# Soldeerboute.net
KiCad netlist of a schematic drawn in Altium Designer
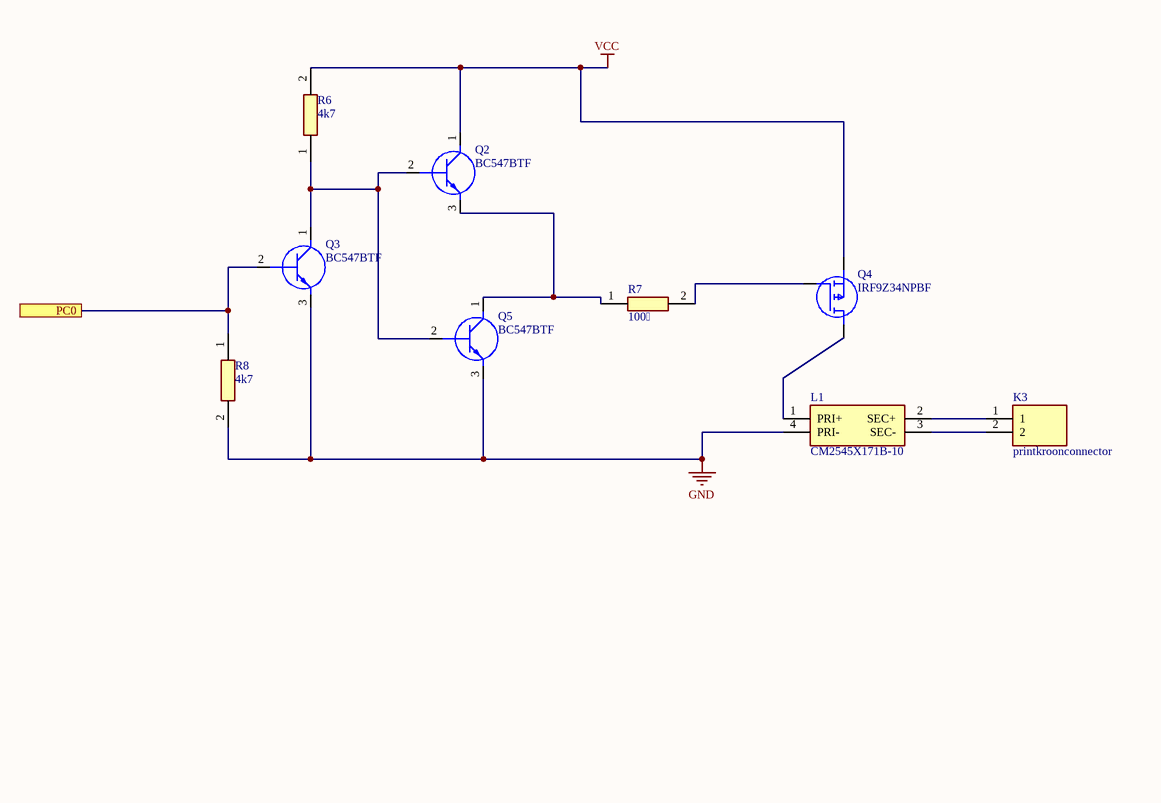
[diagram p0: Soldeerboute.SchDoc]

(export (version "E")
  (design (tool "Eeschema 10.0.6"))
  (components
    (comp (ref "K3")
      (value "printkroonconnector")
      (footprint "SamacSys:1729128")
      (description "Connector")
      (fields (field (name "MANUFACTURER_PART_NUMBER") "1729128"))
      (libsource (lib "Schlib_soldeerbout") (part "printkroonconnector"))
    )
    (comp (ref "L1")
      (value "CM2545X171B-10")
      (footprint "SamacSys:CM2545X171B10")
      (description "Transformer")
      (libsource (lib "Schlib_soldeerbout") (part "CM2545X171B-10"))
    )
    (comp (ref "Q2")
      (value "BC547BTF")
      (footprint "SamacSys:BC33740TA")
      (description "Transistor BJT NPN")
      (libsource (lib "Schlib_soldeerbout") (part "BC547BTF"))
    )
    (comp (ref "Q3")
      (value "BC547BTF")
      (footprint "SamacSys:BC33740TA")
      (description "Transistor BJT NPN")
      (libsource (lib "Schlib_soldeerbout") (part "BC547BTF"))
    )
    (comp (ref "Q4")
      (value "IRF9Z34NPBF")
      (footprint "SamacSys:TO254P469X1042X1967-3P")
      (description "MOSFET (P-Channel)")
      (fields (field (name "MOUSER2 PART NUMBER") "942-IRF9Z34NPBF"))
      (libsource (lib "Schlib_soldeerbout") (part "IRF9Z34NPBF"))
    )
    (comp (ref "Q5")
      (value "BC547BTF")
      (footprint "SamacSys:BC33740TA")
      (description "Transistor BJT NPN")
      (libsource (lib "Schlib_soldeerbout") (part "BC547BTF"))
    )
    (comp (ref "R6")
      (value "4k7")
      (footprint "SamacSys:RESC2012X65N")
      (description "Resistor")
      (fields (field (name "MANUFACTURER_PART_NUMBER") "ESR10EZPJ183"))
      (libsource (lib "Schlib_soldeerbout") (part "ESR10EZPJ183"))
    )
    (comp (ref "R7")
      (value "100")
      (footprint "SamacSys:RESC2012X65N")
      (description "Resistor")
      (fields (field (name "MANUFACTURER_PART_NUMBER") "ESR10EZPJ183"))
      (libsource (lib "") (part "ESR10EZPJ183_2"))
    )
    (comp (ref "R8")
      (value "4k7")
      (footprint "SamacSys:RESC2012X65N")
      (description "Resistor")
      (fields (field (name "MANUFACTURER_PART_NUMBER") "ESR10EZPJ183"))
      (libsource (lib "") (part "ESR10EZPJ183_1"))
    )
  )
  (nets
    (net (code "1") (name "/PC0") (class "Default")
      (node (ref "Q3") (pin "2") (pinfunction "B_2") (pintype "passive"))
      (node (ref "R8") (pin "1") (pinfunction "1_1") (pintype "passive"))
    )
    (net (code "2") (name "GND") (class "Default")
      (node (ref "L1") (pin "4") (pinfunction "PRI-_4") (pintype "passive"))
      (node (ref "Q3") (pin "3") (pinfunction "E_3") (pintype "passive"))
      (node (ref "Q5") (pin "3") (pinfunction "E_3") (pintype "passive"))
      (node (ref "R8") (pin "2") (pinfunction "2_2") (pintype "passive"))
    )
    (net (code "3") (name "Net-(L1-PRI+)") (class "Default")
      (node (ref "L1") (pin "1") (pinfunction "PRI+_1") (pintype "passive"))
      (node (ref "Q4") (pin "3") (pinfunction "D_3") (pintype "passive"))
    )
    (net (code "4") (name "Net-(L1-SEC+)") (class "Default")
      (node (ref "K3") (pin "1") (pinfunction "1_1") (pintype "passive"))
      (node (ref "L1") (pin "2") (pinfunction "SEC+_2") (pintype "passive"))
    )
    (net (code "5") (name "Net-(L1-SEC-)") (class "Default")
      (node (ref "K3") (pin "2") (pinfunction "2_2") (pintype "passive"))
      (node (ref "L1") (pin "3") (pinfunction "SEC-_3") (pintype "passive"))
    )
    (net (code "6") (name "Net-(Q2-B)") (class "Default")
      (node (ref "Q2") (pin "2") (pinfunction "B_2") (pintype "passive"))
      (node (ref "Q3") (pin "1") (pinfunction "C_1") (pintype "passive"))
      (node (ref "Q5") (pin "2") (pinfunction "B_2") (pintype "passive"))
      (node (ref "R6") (pin "1") (pinfunction "1_1") (pintype "passive"))
    )
    (net (code "7") (name "Net-(Q2-E)") (class "Default")
      (node (ref "Q2") (pin "3") (pinfunction "E_3") (pintype "passive"))
      (node (ref "Q5") (pin "1") (pinfunction "C_1") (pintype "passive"))
      (node (ref "R7") (pin "1") (pinfunction "1_1") (pintype "passive"))
    )
    (net (code "8") (name "Net-(Q4-G)") (class "Default")
      (node (ref "Q4") (pin "1") (pinfunction "G_1") (pintype "passive"))
      (node (ref "R7") (pin "2") (pinfunction "2_2") (pintype "passive"))
    )
    (net (code "9") (name "VCC") (class "Default")
      (node (ref "Q2") (pin "1") (pinfunction "C_1") (pintype "passive"))
      (node (ref "Q4") (pin "2") (pinfunction "S_2") (pintype "passive"))
      (node (ref "R6") (pin "2") (pinfunction "2_2") (pintype "passive"))
    )
  )
)
